# CanAndSupply.net
KiCad netlist of a schematic drawn in Altium Designer
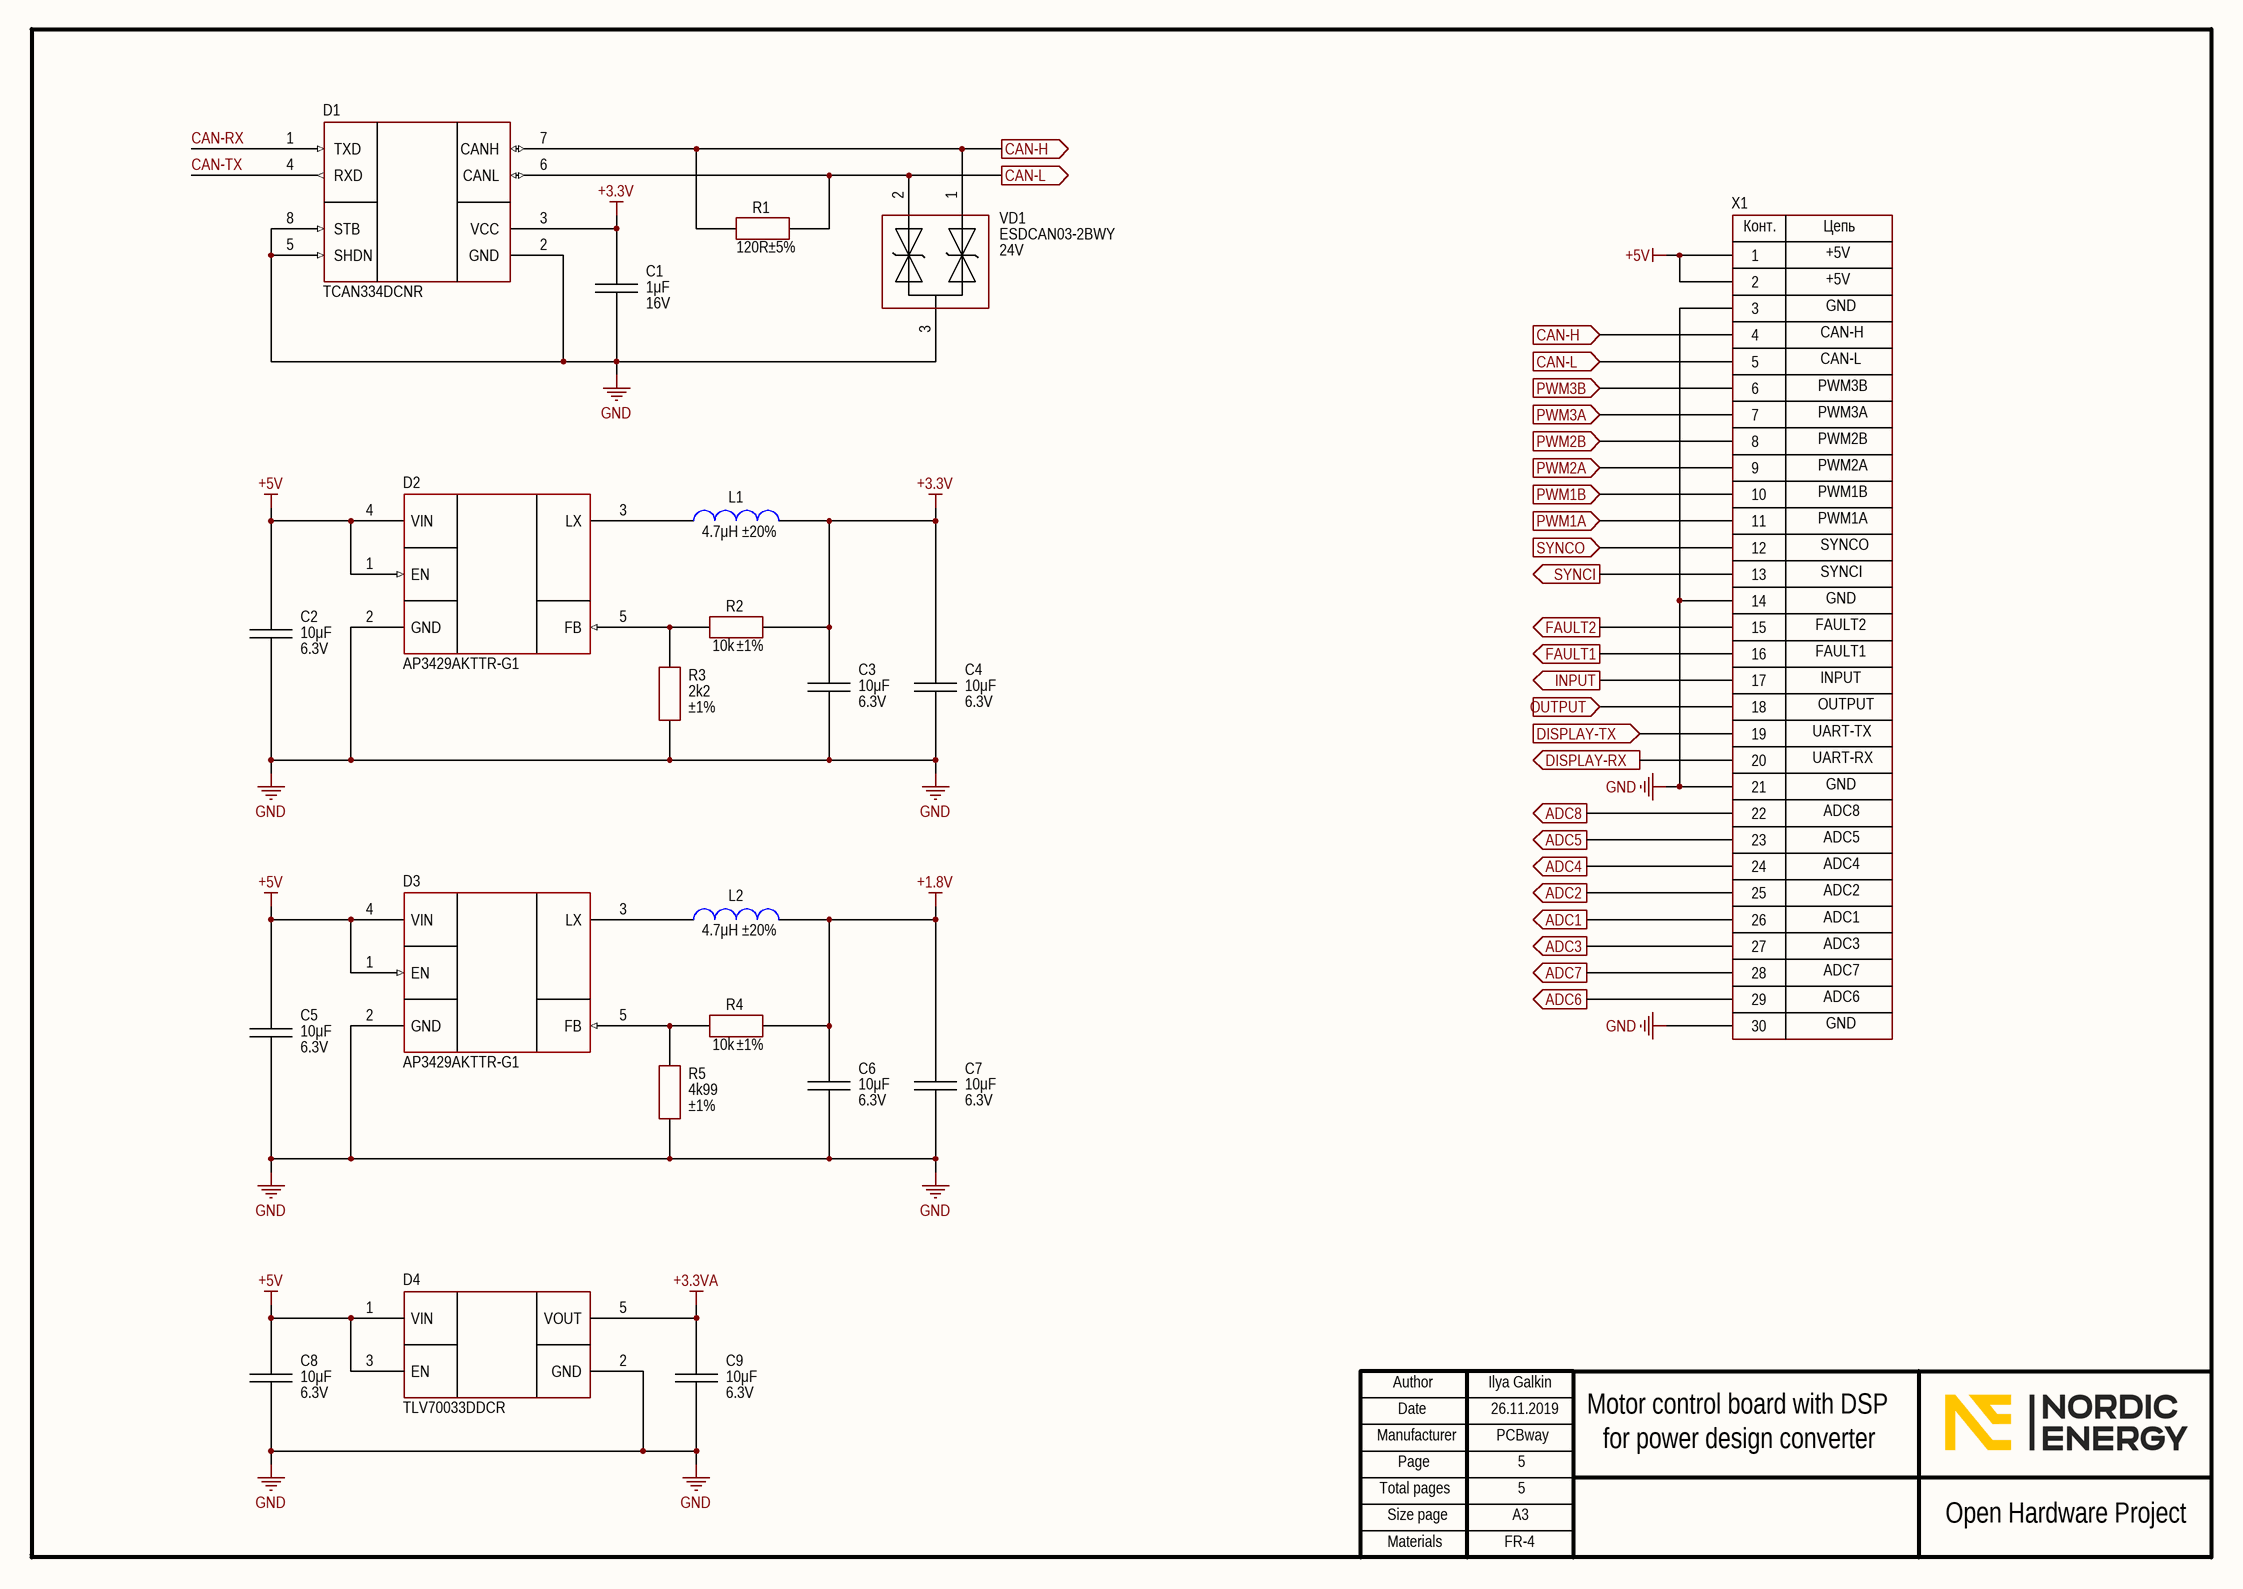
[diagram p0: CanAndSupply.SchDoc]

(export (version "E")
  (design (tool "Eeschema 10.0.6"))
  (components
    (comp (ref "C1")
      (value "1μF")
      (footprint "CAP: 0603")
      (fields
        (field (name "MANUFACTURER") "Samsung")
        (field (name "PARTNUMBER") "CL10B105KO8NNNC")
        (field (name "VALUEMANUFACTURERPARTNUMBER") "Ceramic capacitor, 1μF, X7R, ±10%, 16V, 0603, -55...+125°C")
        (field (name "VOLTAGE") "16V")
      )
      (libsource (lib "Capacitor") (part "Ceramic_0603"))
    )
    (comp (ref "C2")
      (value "10μF")
      (footprint "CAP: 0603")
      (fields
        (field (name "MANUFACTURER") "Samsung")
        (field (name "PARTNUMBER") "CL10B106MQ8NRNC")
        (field (name "VALUEMANUFACTURERPARTNUMBER") "Ceramic capacitor, 10μF, X7R, ±10%, 6.3V, 0603, -55...+125°C")
        (field (name "VOLTAGE") "6.3V")
      )
      (libsource (lib "Capacitor") (part "Ceramic_0603"))
    )
    (comp (ref "C3")
      (value "10μF")
      (footprint "CAP: 0603")
      (fields
        (field (name "MANUFACTURER") "Samsung")
        (field (name "PARTNUMBER") "CL10B106MQ8NRNC")
        (field (name "VALUEMANUFACTURERPARTNUMBER") "Ceramic capacitor, 10μF, X7R, ±10%, 6.3V, 0603, -55...+125°C")
        (field (name "VOLTAGE") "6.3V")
      )
      (libsource (lib "Capacitor") (part "Ceramic_0603"))
    )
    (comp (ref "C4")
      (value "10μF")
      (footprint "CAP: 0603")
      (fields
        (field (name "MANUFACTURER") "Samsung")
        (field (name "PARTNUMBER") "CL10B106MQ8NRNC")
        (field (name "VALUEMANUFACTURERPARTNUMBER") "Ceramic capacitor, 10μF, X7R, ±10%, 6.3V, 0603, -55...+125°C")
        (field (name "VOLTAGE") "6.3V")
      )
      (libsource (lib "Capacitor") (part "Ceramic_0603"))
    )
    (comp (ref "C5")
      (value "10μF")
      (footprint "CAP: 0603")
      (fields
        (field (name "MANUFACTURER") "Samsung")
        (field (name "PARTNUMBER") "CL10B106MQ8NRNC")
        (field (name "VALUEMANUFACTURERPARTNUMBER") "Ceramic capacitor, 10μF, X7R, ±10%, 6.3V, 0603, -55...+125°C")
        (field (name "VOLTAGE") "6.3V")
      )
      (libsource (lib "Capacitor") (part "Ceramic_0603"))
    )
    (comp (ref "C6")
      (value "10μF")
      (footprint "CAP: 0603")
      (fields
        (field (name "MANUFACTURER") "Samsung")
        (field (name "PARTNUMBER") "CL10B106MQ8NRNC")
        (field (name "VALUEMANUFACTURERPARTNUMBER") "Ceramic capacitor, 10μF, X7R, ±10%, 6.3V, 0603, -55...+125°C")
        (field (name "VOLTAGE") "6.3V")
      )
      (libsource (lib "Capacitor") (part "Ceramic_0603"))
    )
    (comp (ref "C7")
      (value "10μF")
      (footprint "CAP: 0603")
      (fields
        (field (name "MANUFACTURER") "Samsung")
        (field (name "PARTNUMBER") "CL10B106MQ8NRNC")
        (field (name "VALUEMANUFACTURERPARTNUMBER") "Ceramic capacitor, 10μF, X7R, ±10%, 6.3V, 0603, -55...+125°C")
        (field (name "VOLTAGE") "6.3V")
      )
      (libsource (lib "Capacitor") (part "Ceramic_0603"))
    )
    (comp (ref "C8")
      (value "10μF")
      (footprint "CAP: 0603")
      (fields
        (field (name "MANUFACTURER") "Samsung")
        (field (name "PARTNUMBER") "CL10B106MQ8NRNC")
        (field (name "VALUEMANUFACTURERPARTNUMBER") "Ceramic capacitor, 10μF, X7R, ±10%, 6.3V, 0603, -55...+125°C")
        (field (name "VOLTAGE") "6.3V")
      )
      (libsource (lib "Capacitor") (part "Ceramic_0603"))
    )
    (comp (ref "C9")
      (value "10μF")
      (footprint "CAP: 0603")
      (fields
        (field (name "MANUFACTURER") "Samsung")
        (field (name "PARTNUMBER") "CL10B106MQ8NRNC")
        (field (name "VALUEMANUFACTURERPARTNUMBER") "Ceramic capacitor, 10μF, X7R, ±10%, 6.3V, 0603, -55...+125°C")
        (field (name "VOLTAGE") "6.3V")
      )
      (libsource (lib "Capacitor") (part "Ceramic_0603"))
    )
    (comp (ref "D1")
      (value "~")
      (footprint "SOT23-8")
      (description "CAN")
      (fields
        (field (name "MANUFACTURER") "Texas Instruments")
        (field (name "VALUEMANUFACTURERPARTNUMBER") "IC CAN transceiver, 1Mbps, Half-duplex, 3...3.6V, -40...+125°C, SOT23-8")
        (field (name "PARTNUMBER") "TCAN334DCNR")
      )
      (libsource (lib "IC. Interface") (part "TCAN334DCNR"))
    )
    (comp (ref "D2")
      (value "~")
      (footprint "SOT23-5")
      (description "Buck converter")
      (fields
        (field (name "MANUFACTURER") "Diodes Incorporated")
        (field (name "VALUEMANUFACTURERPARTNUMBER") "DC/DC buck converter, input 2.7...5.5V, 1MHz, output 0.6...5V, 2A, -40...+85°C, SOT23-6")
        (field (name "PARTNUMBER") "AP3429AKTTR-G1")
      )
      (libsource (lib "IC. Power supply") (part "AP3429AKTTR-G1"))
    )
    (comp (ref "D3")
      (value "~")
      (footprint "SOT23-5")
      (description "Buck converter")
      (fields
        (field (name "MANUFACTURER") "Diodes Incorporated")
        (field (name "VALUEMANUFACTURERPARTNUMBER") "DC/DC buck converter, input 2.7...5.5V, 1MHz, output 0.6...5V, 2A, -40...+85°C, SOT23-6")
        (field (name "PARTNUMBER") "AP3429AKTTR-G1")
      )
      (libsource (lib "IC. Power supply") (part "AP3429AKTTR-G1"))
    )
    (comp (ref "D4")
      (value "~")
      (footprint "SOT23-5")
      (description "Linear voltage regulator")
      (fields
        (field (name "MANUFACTURER") "Texas Instruments")
        (field (name "VALUEMANUFACTURERPARTNUMBER") "Linear voltage regulator, input 5.5V, 0.25V, output 3.3V, 200 mA, -40...+85°C, SOT-23-5")
        (field (name "PARTNUMBER") "TLV70033DDCR")
      )
      (libsource (lib "IC. Power supply") (part "TLV70033DDCR"))
    )
    (comp (ref "L1")
      (value "4.7μH")
      (footprint "IND: SRP2510A")
      (fields
        (field (name "MANUFACTURER") "Bourns")
        (field (name "PARTNUMBER") "SRP2510A-4R7M")
        (field (name "VALUEMANUFACTURERPARTNUMBER") "Fixed inductor, 4.7μH, ±20%, SRP2510A, 1.36A, -40...+125°C")
        (field (name "TOLERANCE") "±20%")
      )
      (libsource (lib "Inductor") (part "Inductor_SRP2510A"))
    )
    (comp (ref "L2")
      (value "4.7μH")
      (footprint "IND: SRP2510A")
      (fields
        (field (name "MANUFACTURER") "Bourns")
        (field (name "PARTNUMBER") "SRP2510A-4R7M")
        (field (name "VALUEMANUFACTURERPARTNUMBER") "Fixed inductor, 4.7μH, ±20%, SRP2510A, 1.36A, -40...+125°C")
        (field (name "TOLERANCE") "±20%")
      )
      (libsource (lib "Inductor") (part "Inductor_SRP2510A"))
    )
    (comp (ref "R1")
      (value "120R")
      (footprint "RES: 0603")
      (fields
        (field (name "MANUFACTURER") "Yageo")
        (field (name "PARTNUMBER") "RC0603JR-07120RL")
        (field (name "VALUEMANUFACTURERPARTNUMBER") "Resistor film, 120R, ±5%, 0603, 0.1W, -55...+125°C")
        (field (name "TOLERANCE") "±5%")
      )
      (libsource (lib "") (part "Resistor_0603_2"))
    )
    (comp (ref "R2")
      (value "10k")
      (footprint "RES: 0603")
      (fields
        (field (name "MANUFACTURER") "Yageo")
        (field (name "PARTNUMBER") "RC0603FR-0710KL")
        (field (name "VALUEMANUFACTURERPARTNUMBER") "Resistor film, 10k, ±1%, 0603, 0.1W, -55...+125°C")
        (field (name "TOLERANCE") "±1%")
      )
      (libsource (lib "Resistor") (part "Resistor_0603"))
    )
    (comp (ref "R3")
      (value "2k2")
      (footprint "RES: 0603")
      (fields
        (field (name "MANUFACTURER") "Yageo")
        (field (name "PARTNUMBER") "RC0603FR-072K2L")
        (field (name "VALUEMANUFACTURERPARTNUMBER") "Resistor film, 2k2, ±1%, 0603, 0.1W, -55...+125°C")
        (field (name "TOLERANCE") "±1%")
      )
      (libsource (lib "") (part "Resistor_0603_1"))
    )
    (comp (ref "R4")
      (value "10k")
      (footprint "RES: 0603")
      (fields
        (field (name "MANUFACTURER") "Yageo")
        (field (name "PARTNUMBER") "RC0603FR-0710KL")
        (field (name "VALUEMANUFACTURERPARTNUMBER") "Resistor film, 10k, ±1%, 0603, 0.1W, -55...+125°C")
        (field (name "TOLERANCE") "±1%")
      )
      (libsource (lib "Resistor") (part "Resistor_0603"))
    )
    (comp (ref "R5")
      (value "4k99")
      (footprint "RES: 0603")
      (fields
        (field (name "MANUFACTURER") "Yageo")
        (field (name "PARTNUMBER") "RC0603FR-074K99L")
        (field (name "VALUEMANUFACTURERPARTNUMBER") "Resistor film, 4k99, ±1%, 0603, 0.1W, -55...+125°C")
        (field (name "TOLERANCE") "±1%")
      )
      (libsource (lib "") (part "Resistor_0603_1"))
    )
    (comp (ref "VD1")
      (value "~")
      (footprint "SC-70")
      (fields
        (field (name "MANUFACTURER") "Texas Instruments")
        (field (name "VALUEMANUFACTURERPARTNUMBER") "Zener diode, 24V, 250W, 3A peak, 3pF, SC-70, -55...+175°C")
        (field (name "VOLTAGE") "24V")
        (field (name "PARTNUMBER") "ESDCAN03-2BWY")
      )
      (libsource (lib "Diode") (part "TVS_array"))
    )
    (comp (ref "X1")
      (value "~")
      (footprint "CON: PLS-30R")
      (fields
        (field (name "MANUFACTURER") "Connfly")
        (field (name "VALUEMANUFACTURERPARTNUMBER") "Connector, 30pin, 2.54mm, 500VAC, 3A")
        (field (name "PARTNUMBER") "PLS-30")
      )
      (libsource (lib "Connector") (part "PLS-30"))
    )
  )
  (nets
    (net (code "1") (name "+1.8V") (class "Default")
      (node (ref "C6") (pin "2") (pinfunction "2_2") (pintype "power_in"))
      (node (ref "C7") (pin "2") (pinfunction "2_2") (pintype "power_in"))
      (node (ref "L2") (pin "1") (pinfunction "1_1") (pintype "passive"))
      (node (ref "R4") (pin "1") (pinfunction "1_1") (pintype "passive"))
    )
    (net (code "2") (name "+3.3V") (class "Default")
      (node (ref "C1") (pin "2") (pinfunction "2_2") (pintype "power_in"))
      (node (ref "C3") (pin "2") (pinfunction "2_2") (pintype "power_in"))
      (node (ref "C4") (pin "2") (pinfunction "2_2") (pintype "power_in"))
      (node (ref "D1") (pin "3") (pinfunction "VCC_3") (pintype "passive"))
      (node (ref "L1") (pin "1") (pinfunction "1_1") (pintype "passive"))
      (node (ref "R2") (pin "1") (pinfunction "1_1") (pintype "passive"))
    )
    (net (code "3") (name "+3.3VA") (class "Default")
      (node (ref "C9") (pin "2") (pinfunction "2_2") (pintype "power_in"))
      (node (ref "D4") (pin "5") (pinfunction "VOUT_5") (pintype "passive"))
    )
    (net (code "4") (name "+5V") (class "Default")
      (node (ref "C2") (pin "2") (pinfunction "2_2") (pintype "power_in"))
      (node (ref "C5") (pin "2") (pinfunction "2_2") (pintype "power_in"))
      (node (ref "C8") (pin "2") (pinfunction "2_2") (pintype "power_in"))
      (node (ref "D2") (pin "1") (pinfunction "EN_1") (pintype "input"))
      (node (ref "D2") (pin "4") (pinfunction "VIN_4") (pintype "passive"))
      (node (ref "D3") (pin "1") (pinfunction "EN_1") (pintype "input"))
      (node (ref "D3") (pin "4") (pinfunction "VIN_4") (pintype "passive"))
      (node (ref "D4") (pin "1") (pinfunction "VIN_1") (pintype "passive"))
      (node (ref "D4") (pin "3") (pinfunction "EN_3") (pintype "passive"))
      (node (ref "X1") (pin "1") (pinfunction "1_1") (pintype "passive"))
      (node (ref "X1") (pin "2") (pinfunction "2_2") (pintype "passive"))
    )
    (net (code "5") (name "/ADC1") (class "Default")
      (node (ref "X1") (pin "26") (pinfunction "26_26") (pintype "passive"))
    )
    (net (code "6") (name "/ADC2") (class "Default")
      (node (ref "X1") (pin "25") (pinfunction "25_25") (pintype "passive"))
    )
    (net (code "7") (name "/ADC3") (class "Default")
      (node (ref "X1") (pin "27") (pinfunction "27_27") (pintype "passive"))
    )
    (net (code "8") (name "/ADC4") (class "Default")
      (node (ref "X1") (pin "24") (pinfunction "24_24") (pintype "passive"))
    )
    (net (code "9") (name "/ADC5") (class "Default")
      (node (ref "X1") (pin "23") (pinfunction "23_23") (pintype "passive"))
    )
    (net (code "10") (name "/ADC6") (class "Default")
      (node (ref "X1") (pin "29") (pinfunction "29_29") (pintype "passive"))
    )
    (net (code "11") (name "/ADC7") (class "Default")
      (node (ref "X1") (pin "28") (pinfunction "28_28") (pintype "passive"))
    )
    (net (code "12") (name "/ADC8") (class "Default")
      (node (ref "X1") (pin "22") (pinfunction "22_22") (pintype "passive"))
    )
    (net (code "13") (name "/CAN-H") (class "Default")
      (node (ref "D1") (pin "7") (pinfunction "CANH_7") (pintype "bidirectional"))
      (node (ref "R1") (pin "1") (pinfunction "1_1") (pintype "passive"))
      (node (ref "VD1") (pin "1") (pintype "passive"))
      (node (ref "X1") (pin "4") (pinfunction "4_4") (pintype "passive"))
    )
    (net (code "14") (name "/CAN-L") (class "Default")
      (node (ref "D1") (pin "6") (pinfunction "CANL_6") (pintype "bidirectional"))
      (node (ref "R1") (pin "2") (pinfunction "2_2") (pintype "passive"))
      (node (ref "VD1") (pin "2") (pintype "passive"))
      (node (ref "X1") (pin "5") (pinfunction "5_5") (pintype "passive"))
    )
    (net (code "15") (name "/CAN-RX") (class "Default")
      (node (ref "D1") (pin "1") (pinfunction "TXD_1") (pintype "input"))
    )
    (net (code "16") (name "/CAN-TX") (class "Default")
      (node (ref "D1") (pin "4") (pinfunction "RXD_4") (pintype "output"))
    )
    (net (code "17") (name "/DISPLAY-RX") (class "Default")
      (node (ref "X1") (pin "20") (pinfunction "20_20") (pintype "passive"))
    )
    (net (code "18") (name "/DISPLAY-TX") (class "Default")
      (node (ref "X1") (pin "19") (pinfunction "19_19") (pintype "passive"))
    )
    (net (code "19") (name "/FAULT1") (class "Default")
      (node (ref "X1") (pin "16") (pinfunction "16_16") (pintype "passive"))
    )
    (net (code "20") (name "/FAULT2") (class "Default")
      (node (ref "X1") (pin "15") (pinfunction "15_15") (pintype "passive"))
    )
    (net (code "21") (name "/INPUT") (class "Default")
      (node (ref "X1") (pin "17") (pinfunction "17_17") (pintype "passive"))
    )
    (net (code "22") (name "/OUTPUT") (class "Default")
      (node (ref "X1") (pin "18") (pinfunction "18_18") (pintype "passive"))
    )
    (net (code "23") (name "/PWM1A") (class "Default")
      (node (ref "X1") (pin "11") (pinfunction "11_11") (pintype "passive"))
    )
    (net (code "24") (name "/PWM1B") (class "Default")
      (node (ref "X1") (pin "10") (pinfunction "10_10") (pintype "passive"))
    )
    (net (code "25") (name "/PWM2A") (class "Default")
      (node (ref "X1") (pin "9") (pinfunction "9_9") (pintype "passive"))
    )
    (net (code "26") (name "/PWM2B") (class "Default")
      (node (ref "X1") (pin "8") (pinfunction "8_8") (pintype "passive"))
    )
    (net (code "27") (name "/PWM3A") (class "Default")
      (node (ref "X1") (pin "7") (pinfunction "7_7") (pintype "passive"))
    )
    (net (code "28") (name "/PWM3B") (class "Default")
      (node (ref "X1") (pin "6") (pinfunction "6_6") (pintype "passive"))
    )
    (net (code "29") (name "/SYNCI") (class "Default")
      (node (ref "X1") (pin "13") (pinfunction "13_13") (pintype "passive"))
    )
    (net (code "30") (name "/SYNCO") (class "Default")
      (node (ref "X1") (pin "12") (pinfunction "12_12") (pintype "passive"))
    )
    (net (code "31") (name "GND") (class "Default")
      (node (ref "C1") (pin "1") (pinfunction "1_1") (pintype "power_in"))
      (node (ref "C2") (pin "1") (pinfunction "1_1") (pintype "power_in"))
      (node (ref "C3") (pin "1") (pinfunction "1_1") (pintype "power_in"))
      (node (ref "C4") (pin "1") (pinfunction "1_1") (pintype "power_in"))
      (node (ref "C5") (pin "1") (pinfunction "1_1") (pintype "power_in"))
      (node (ref "C6") (pin "1") (pinfunction "1_1") (pintype "power_in"))
      (node (ref "C7") (pin "1") (pinfunction "1_1") (pintype "power_in"))
      (node (ref "C8") (pin "1") (pinfunction "1_1") (pintype "power_in"))
      (node (ref "C9") (pin "1") (pinfunction "1_1") (pintype "power_in"))
      (node (ref "D1") (pin "2") (pinfunction "GND_2") (pintype "passive"))
      (node (ref "D1") (pin "5") (pinfunction "SHDN_5") (pintype "input"))
      (node (ref "D1") (pin "8") (pinfunction "STB_8") (pintype "input"))
      (node (ref "D2") (pin "2") (pinfunction "GND_2") (pintype "passive"))
      (node (ref "D3") (pin "2") (pinfunction "GND_2") (pintype "passive"))
      (node (ref "D4") (pin "2") (pinfunction "GND_2") (pintype "passive"))
      (node (ref "R3") (pin "1") (pinfunction "1_1") (pintype "passive"))
      (node (ref "R5") (pin "1") (pinfunction "1_1") (pintype "passive"))
      (node (ref "VD1") (pin "3") (pintype "passive"))
      (node (ref "X1") (pin "14") (pinfunction "14_14") (pintype "passive"))
      (node (ref "X1") (pin "21") (pinfunction "21_21") (pintype "passive"))
      (node (ref "X1") (pin "3") (pinfunction "3_3") (pintype "passive"))
      (node (ref "X1") (pin "30") (pinfunction "30_30") (pintype "passive"))
    )
    (net (code "32") (name "Net-(D2-FB)") (class "Default")
      (node (ref "D2") (pin "5") (pinfunction "FB_5") (pintype "input"))
      (node (ref "R2") (pin "2") (pinfunction "2_2") (pintype "passive"))
      (node (ref "R3") (pin "2") (pinfunction "2_2") (pintype "passive"))
    )
    (net (code "33") (name "Net-(D2-LX)") (class "Default")
      (node (ref "D2") (pin "3") (pinfunction "LX_3") (pintype "passive"))
      (node (ref "L1") (pin "2") (pinfunction "2_2") (pintype "passive"))
    )
    (net (code "34") (name "Net-(D3-FB)") (class "Default")
      (node (ref "D3") (pin "5") (pinfunction "FB_5") (pintype "input"))
      (node (ref "R4") (pin "2") (pinfunction "2_2") (pintype "passive"))
      (node (ref "R5") (pin "2") (pinfunction "2_2") (pintype "passive"))
    )
    (net (code "35") (name "Net-(D3-LX)") (class "Default")
      (node (ref "D3") (pin "3") (pinfunction "LX_3") (pintype "passive"))
      (node (ref "L2") (pin "2") (pinfunction "2_2") (pintype "passive"))
    )
  )
)
